# S107X.net
KiCad netlist of a schematic drawn in EAGLE
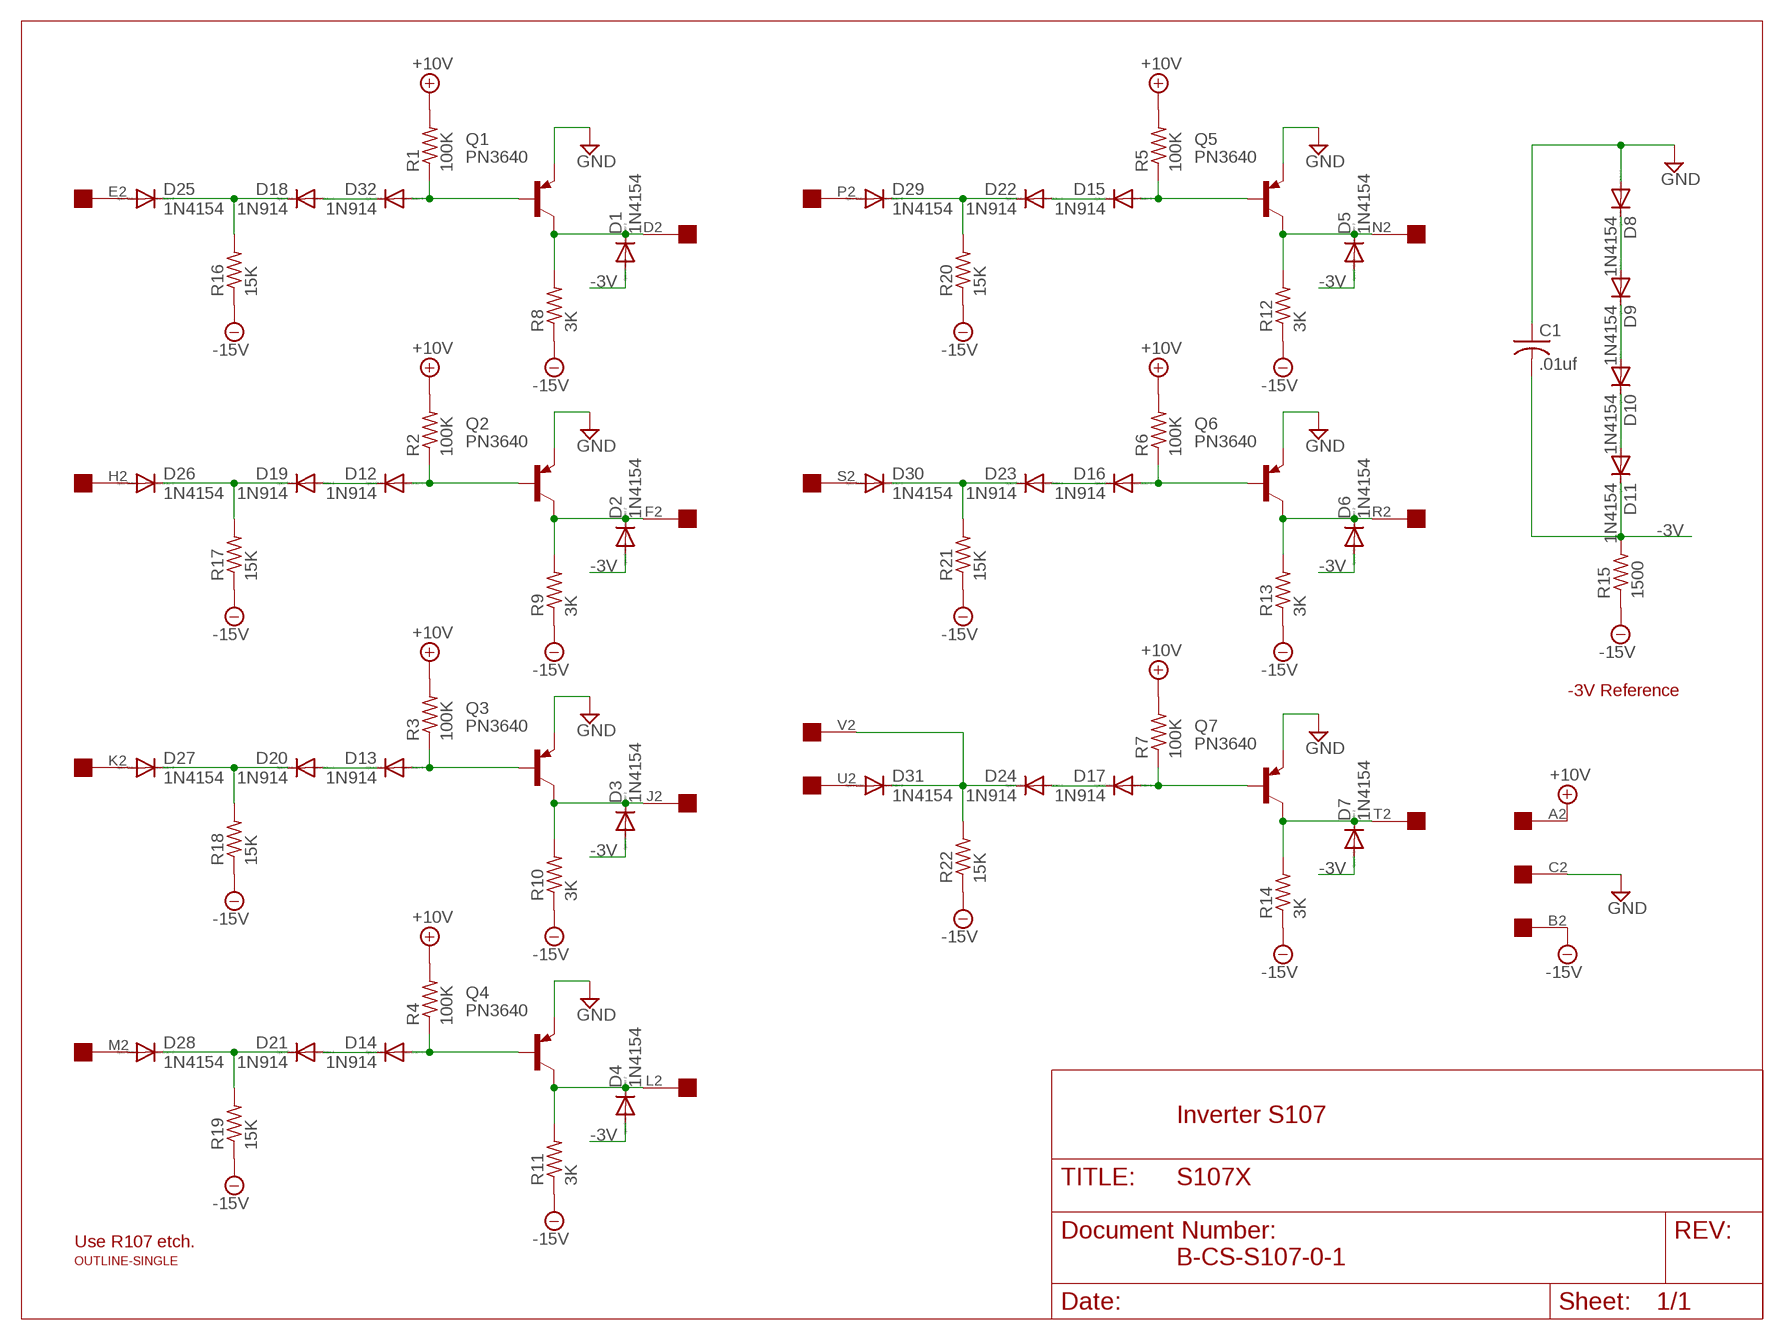
[diagram p0: schematic, sheet 1]

(export (version "E")
  (design (tool "Eeschema 10.0.6"))
  (components
    (comp (ref "C1")
      (value ".01uf")
      (footprint "eagle-import:C050-025X075")
      (libsource (lib "eagle-import") (part "C-US050-025X075"))
    )
    (comp (ref "D1")
      (value "1N4154")
      (footprint "eagle-import:DO35-10")
      (libsource (lib "eagle-import") (part "1N4148DO35-10"))
    )
    (comp (ref "D2")
      (value "1N4154")
      (footprint "eagle-import:DO35-10")
      (libsource (lib "eagle-import") (part "1N4148DO35-10"))
    )
    (comp (ref "D3")
      (value "1N4154")
      (footprint "eagle-import:DO35-10")
      (libsource (lib "eagle-import") (part "1N4148DO35-10"))
    )
    (comp (ref "D4")
      (value "1N4154")
      (footprint "eagle-import:DO35-10")
      (libsource (lib "eagle-import") (part "1N4148DO35-10"))
    )
    (comp (ref "D5")
      (value "1N4154")
      (footprint "eagle-import:DO35-10")
      (libsource (lib "eagle-import") (part "1N4148DO35-10"))
    )
    (comp (ref "D6")
      (value "1N4154")
      (footprint "eagle-import:DO35-10")
      (libsource (lib "eagle-import") (part "1N4148DO35-10"))
    )
    (comp (ref "D7")
      (value "1N4154")
      (footprint "eagle-import:DO35-10")
      (libsource (lib "eagle-import") (part "1N4148DO35-10"))
    )
    (comp (ref "D8")
      (value "1N4154")
      (footprint "eagle-import:DO35-10")
      (libsource (lib "eagle-import") (part "1N4148DO35-10"))
    )
    (comp (ref "D9")
      (value "1N4154")
      (footprint "eagle-import:DO35-10")
      (libsource (lib "eagle-import") (part "1N4148DO35-10"))
    )
    (comp (ref "D10")
      (value "1N4154")
      (footprint "eagle-import:DO35-10")
      (libsource (lib "eagle-import") (part "1N4148DO35-10"))
    )
    (comp (ref "D11")
      (value "1N4154")
      (footprint "eagle-import:DO35-10")
      (libsource (lib "eagle-import") (part "1N4148DO35-10"))
    )
    (comp (ref "D12")
      (value "1N914")
      (footprint "eagle-import:DO35-10")
      (libsource (lib "eagle-import") (part "1N4148DO35-10"))
    )
    (comp (ref "D13")
      (value "1N914")
      (footprint "eagle-import:DO35-10")
      (libsource (lib "eagle-import") (part "1N4148DO35-10"))
    )
    (comp (ref "D14")
      (value "1N914")
      (footprint "eagle-import:DO35-10")
      (libsource (lib "eagle-import") (part "1N4148DO35-10"))
    )
    (comp (ref "D15")
      (value "1N914")
      (footprint "eagle-import:DO35-10")
      (libsource (lib "eagle-import") (part "1N4148DO35-10"))
    )
    (comp (ref "D16")
      (value "1N914")
      (footprint "eagle-import:DO35-10")
      (libsource (lib "eagle-import") (part "1N4148DO35-10"))
    )
    (comp (ref "D17")
      (value "1N914")
      (footprint "eagle-import:DO35-10")
      (libsource (lib "eagle-import") (part "1N4148DO35-10"))
    )
    (comp (ref "D18")
      (value "1N914")
      (footprint "eagle-import:DO35-10")
      (libsource (lib "eagle-import") (part "1N4148DO35-10"))
    )
    (comp (ref "D19")
      (value "1N914")
      (footprint "eagle-import:DO35-10")
      (libsource (lib "eagle-import") (part "1N4148DO35-10"))
    )
    (comp (ref "D20")
      (value "1N914")
      (footprint "eagle-import:DO35-10")
      (libsource (lib "eagle-import") (part "1N4148DO35-10"))
    )
    (comp (ref "D21")
      (value "1N914")
      (footprint "eagle-import:DO35-10")
      (libsource (lib "eagle-import") (part "1N4148DO35-10"))
    )
    (comp (ref "D22")
      (value "1N914")
      (footprint "eagle-import:DO35-10")
      (libsource (lib "eagle-import") (part "1N4148DO35-10"))
    )
    (comp (ref "D23")
      (value "1N914")
      (footprint "eagle-import:DO35-10")
      (libsource (lib "eagle-import") (part "1N4148DO35-10"))
    )
    (comp (ref "D24")
      (value "1N914")
      (footprint "eagle-import:DO35-10")
      (libsource (lib "eagle-import") (part "1N4148DO35-10"))
    )
    (comp (ref "D25")
      (value "1N4154")
      (footprint "eagle-import:DO35-10")
      (libsource (lib "eagle-import") (part "1N4148DO35-10"))
    )
    (comp (ref "D26")
      (value "1N4154")
      (footprint "eagle-import:DO35-10")
      (libsource (lib "eagle-import") (part "1N4148DO35-10"))
    )
    (comp (ref "D27")
      (value "1N4154")
      (footprint "eagle-import:DO35-10")
      (libsource (lib "eagle-import") (part "1N4148DO35-10"))
    )
    (comp (ref "D28")
      (value "1N4154")
      (footprint "eagle-import:DO35-10")
      (libsource (lib "eagle-import") (part "1N4148DO35-10"))
    )
    (comp (ref "D29")
      (value "1N4154")
      (footprint "eagle-import:DO35-10")
      (libsource (lib "eagle-import") (part "1N4148DO35-10"))
    )
    (comp (ref "D30")
      (value "1N4154")
      (footprint "eagle-import:DO35-10")
      (libsource (lib "eagle-import") (part "1N4148DO35-10"))
    )
    (comp (ref "D31")
      (value "1N4154")
      (footprint "eagle-import:DO35-10")
      (libsource (lib "eagle-import") (part "1N4148DO35-10"))
    )
    (comp (ref "D32")
      (value "1N914")
      (footprint "eagle-import:DO35-10")
      (libsource (lib "eagle-import") (part "1N4148DO35-10"))
    )
    (comp (ref "Q1")
      (value "PN3640")
      (footprint "eagle-import:TO39")
      (libsource (lib "eagle-import") (part "2N3637"))
    )
    (comp (ref "Q2")
      (value "PN3640")
      (footprint "eagle-import:TO39")
      (libsource (lib "eagle-import") (part "2N3637"))
    )
    (comp (ref "Q3")
      (value "PN3640")
      (footprint "eagle-import:TO39")
      (libsource (lib "eagle-import") (part "2N3637"))
    )
    (comp (ref "Q4")
      (value "PN3640")
      (footprint "eagle-import:TO39")
      (libsource (lib "eagle-import") (part "2N3637"))
    )
    (comp (ref "Q5")
      (value "PN3640")
      (footprint "eagle-import:TO39")
      (libsource (lib "eagle-import") (part "2N3637"))
    )
    (comp (ref "Q6")
      (value "PN3640")
      (footprint "eagle-import:TO39")
      (libsource (lib "eagle-import") (part "2N3637"))
    )
    (comp (ref "Q7")
      (value "PN3640")
      (footprint "eagle-import:TO39")
      (libsource (lib "eagle-import") (part "2N3637"))
    )
    (comp (ref "R1")
      (value "100K")
      (footprint "eagle-import:0207_10")
      (libsource (lib "eagle-import") (part "R-US_0207/10"))
    )
    (comp (ref "R2")
      (value "100K")
      (footprint "eagle-import:0207_10")
      (libsource (lib "eagle-import") (part "R-US_0207/10"))
    )
    (comp (ref "R3")
      (value "100K")
      (footprint "eagle-import:0207_10")
      (libsource (lib "eagle-import") (part "R-US_0207/10"))
    )
    (comp (ref "R4")
      (value "100K")
      (footprint "eagle-import:0207_10")
      (libsource (lib "eagle-import") (part "R-US_0207/10"))
    )
    (comp (ref "R5")
      (value "100K")
      (footprint "eagle-import:0207_10")
      (libsource (lib "eagle-import") (part "R-US_0207/10"))
    )
    (comp (ref "R6")
      (value "100K")
      (footprint "eagle-import:0207_10")
      (libsource (lib "eagle-import") (part "R-US_0207/10"))
    )
    (comp (ref "R7")
      (value "100K")
      (footprint "eagle-import:0207_10")
      (libsource (lib "eagle-import") (part "R-US_0207/10"))
    )
    (comp (ref "R8")
      (value "3K")
      (footprint "eagle-import:0207_10")
      (libsource (lib "eagle-import") (part "R-US_0207/10"))
    )
    (comp (ref "R9")
      (value "3K")
      (footprint "eagle-import:0207_10")
      (libsource (lib "eagle-import") (part "R-US_0207/10"))
    )
    (comp (ref "R10")
      (value "3K")
      (footprint "eagle-import:0207_10")
      (libsource (lib "eagle-import") (part "R-US_0207/10"))
    )
    (comp (ref "R11")
      (value "3K")
      (footprint "eagle-import:0207_10")
      (libsource (lib "eagle-import") (part "R-US_0207/10"))
    )
    (comp (ref "R12")
      (value "3K")
      (footprint "eagle-import:0207_10")
      (libsource (lib "eagle-import") (part "R-US_0207/10"))
    )
    (comp (ref "R13")
      (value "3K")
      (footprint "eagle-import:0207_10")
      (libsource (lib "eagle-import") (part "R-US_0207/10"))
    )
    (comp (ref "R14")
      (value "3K")
      (footprint "eagle-import:0207_10")
      (libsource (lib "eagle-import") (part "R-US_0207/10"))
    )
    (comp (ref "R15")
      (value "1500")
      (footprint "eagle-import:0207_10")
      (libsource (lib "eagle-import") (part "R-US_0207/10"))
    )
    (comp (ref "R16")
      (value "15K")
      (footprint "eagle-import:0207_10")
      (libsource (lib "eagle-import") (part "R-US_0207/10"))
    )
    (comp (ref "R17")
      (value "15K")
      (footprint "eagle-import:0207_10")
      (libsource (lib "eagle-import") (part "R-US_0207/10"))
    )
    (comp (ref "R18")
      (value "15K")
      (footprint "eagle-import:0207_10")
      (libsource (lib "eagle-import") (part "R-US_0207/10"))
    )
    (comp (ref "R19")
      (value "15K")
      (footprint "eagle-import:0207_10")
      (libsource (lib "eagle-import") (part "R-US_0207/10"))
    )
    (comp (ref "R20")
      (value "15K")
      (footprint "eagle-import:0207_10")
      (libsource (lib "eagle-import") (part "R-US_0207/10"))
    )
    (comp (ref "R21")
      (value "15K")
      (footprint "eagle-import:0207_10")
      (libsource (lib "eagle-import") (part "R-US_0207/10"))
    )
    (comp (ref "R22")
      (value "15K")
      (footprint "eagle-import:0207_10")
      (libsource (lib "eagle-import") (part "R-US_0207/10"))
    )
    (comp (ref "U$1")
      (value "OUTLINE-SINGLE")
      (footprint "eagle-import:SINGLE")
      (libsource (lib "eagle-import") (part "OUTLINE-SINGLE"))
    )
    (comp (ref "U$2")
      (value "EDGE-1")
      (footprint "eagle-import:EDGE-CON1")
      (libsource (lib "eagle-import") (part "EDGE-1"))
    )
  )
  (nets
    (net (code "1") (name "+10V") (class "Default")
      (node (ref "R1") (pin "2") (pinfunction "2_2") (pintype "passive"))
      (node (ref "R2") (pin "2") (pinfunction "2_2") (pintype "passive"))
      (node (ref "R3") (pin "2") (pinfunction "2_2") (pintype "passive"))
      (node (ref "R4") (pin "2") (pinfunction "2_2") (pintype "passive"))
      (node (ref "R5") (pin "2") (pinfunction "2_2") (pintype "passive"))
      (node (ref "R6") (pin "2") (pinfunction "2_2") (pintype "passive"))
      (node (ref "R7") (pin "2") (pinfunction "2_2") (pintype "passive"))
      (node (ref "U$2") (pin "A2") (pinfunction "1_A2") (pintype "bidirectional"))
    )
    (net (code "2") (name "-15V") (class "Default")
      (node (ref "R10") (pin "1") (pinfunction "1_1") (pintype "passive"))
      (node (ref "R11") (pin "1") (pinfunction "1_1") (pintype "passive"))
      (node (ref "R12") (pin "1") (pinfunction "1_1") (pintype "passive"))
      (node (ref "R13") (pin "1") (pinfunction "1_1") (pintype "passive"))
      (node (ref "R14") (pin "1") (pinfunction "1_1") (pintype "passive"))
      (node (ref "R15") (pin "1") (pinfunction "1_1") (pintype "passive"))
      (node (ref "R16") (pin "1") (pinfunction "1_1") (pintype "passive"))
      (node (ref "R17") (pin "1") (pinfunction "1_1") (pintype "passive"))
      (node (ref "R18") (pin "1") (pinfunction "1_1") (pintype "passive"))
      (node (ref "R19") (pin "1") (pinfunction "1_1") (pintype "passive"))
      (node (ref "R20") (pin "1") (pinfunction "1_1") (pintype "passive"))
      (node (ref "R21") (pin "1") (pinfunction "1_1") (pintype "passive"))
      (node (ref "R22") (pin "1") (pinfunction "1_1") (pintype "passive"))
      (node (ref "R8") (pin "1") (pinfunction "1_1") (pintype "passive"))
      (node (ref "R9") (pin "1") (pinfunction "1_1") (pintype "passive"))
      (node (ref "U$2") (pin "B2") (pinfunction "1_B2") (pintype "bidirectional"))
    )
    (net (code "3") (name "/-3V") (class "Default")
      (node (ref "C1") (pin "2") (pinfunction "2_2") (pintype "passive"))
      (node (ref "D1") (pin "A") (pinfunction "A_A") (pintype "passive"))
      (node (ref "D11") (pin "C") (pinfunction "C_C") (pintype "passive"))
      (node (ref "D2") (pin "A") (pinfunction "A_A") (pintype "passive"))
      (node (ref "D3") (pin "A") (pinfunction "A_A") (pintype "passive"))
      (node (ref "D4") (pin "A") (pinfunction "A_A") (pintype "passive"))
      (node (ref "D5") (pin "A") (pinfunction "A_A") (pintype "passive"))
      (node (ref "D6") (pin "A") (pinfunction "A_A") (pintype "passive"))
      (node (ref "D7") (pin "A") (pinfunction "A_A") (pintype "passive"))
      (node (ref "R15") (pin "2") (pinfunction "2_2") (pintype "passive"))
    )
    (net (code "4") (name "GND") (class "Default")
      (node (ref "C1") (pin "1") (pinfunction "1_1") (pintype "passive"))
      (node (ref "D8") (pin "A") (pinfunction "A_A") (pintype "passive"))
      (node (ref "Q1") (pin "1") (pinfunction "E_1") (pintype "passive"))
      (node (ref "Q2") (pin "1") (pinfunction "E_1") (pintype "passive"))
      (node (ref "Q3") (pin "1") (pinfunction "E_1") (pintype "passive"))
      (node (ref "Q4") (pin "1") (pinfunction "E_1") (pintype "passive"))
      (node (ref "Q5") (pin "1") (pinfunction "E_1") (pintype "passive"))
      (node (ref "Q6") (pin "1") (pinfunction "E_1") (pintype "passive"))
      (node (ref "Q7") (pin "1") (pinfunction "E_1") (pintype "passive"))
      (node (ref "U$2") (pin "C2") (pinfunction "1_C2") (pintype "bidirectional"))
    )
    (net (code "5") (name "Net-(D8-PadC)") (class "Default")
      (node (ref "D8") (pin "C") (pinfunction "C_C") (pintype "passive"))
      (node (ref "D9") (pin "A") (pinfunction "A_A") (pintype "passive"))
    )
    (net (code "6") (name "Net-(D10-PadA)") (class "Default")
      (node (ref "D10") (pin "A") (pinfunction "A_A") (pintype "passive"))
      (node (ref "D9") (pin "C") (pinfunction "C_C") (pintype "passive"))
    )
    (net (code "7") (name "Net-(D10-PadC)") (class "Default")
      (node (ref "D10") (pin "C") (pinfunction "C_C") (pintype "passive"))
      (node (ref "D11") (pin "A") (pinfunction "A_A") (pintype "passive"))
    )
    (net (code "8") (name "Net-(D12-PadC)") (class "Default")
      (node (ref "D12") (pin "C") (pinfunction "C_C") (pintype "passive"))
      (node (ref "D19") (pin "A") (pinfunction "A_A") (pintype "passive"))
    )
    (net (code "9") (name "Net-(D13-PadC)") (class "Default")
      (node (ref "D13") (pin "C") (pinfunction "C_C") (pintype "passive"))
      (node (ref "D20") (pin "A") (pinfunction "A_A") (pintype "passive"))
    )
    (net (code "10") (name "Net-(D14-PadC)") (class "Default")
      (node (ref "D14") (pin "C") (pinfunction "C_C") (pintype "passive"))
      (node (ref "D21") (pin "A") (pinfunction "A_A") (pintype "passive"))
    )
    (net (code "11") (name "Net-(D15-PadC)") (class "Default")
      (node (ref "D15") (pin "C") (pinfunction "C_C") (pintype "passive"))
      (node (ref "D22") (pin "A") (pinfunction "A_A") (pintype "passive"))
    )
    (net (code "12") (name "Net-(D16-PadC)") (class "Default")
      (node (ref "D16") (pin "C") (pinfunction "C_C") (pintype "passive"))
      (node (ref "D23") (pin "A") (pinfunction "A_A") (pintype "passive"))
    )
    (net (code "13") (name "Net-(D17-PadC)") (class "Default")
      (node (ref "D17") (pin "C") (pinfunction "C_C") (pintype "passive"))
      (node (ref "D24") (pin "A") (pinfunction "A_A") (pintype "passive"))
    )
    (net (code "14") (name "Net-(D18-PadA)") (class "Default")
      (node (ref "D18") (pin "A") (pinfunction "A_A") (pintype "passive"))
      (node (ref "D32") (pin "C") (pinfunction "C_C") (pintype "passive"))
    )
    (net (code "15") (name "Net-(D18-PadC)") (class "Default")
      (node (ref "D18") (pin "C") (pinfunction "C_C") (pintype "passive"))
      (node (ref "D25") (pin "C") (pinfunction "C_C") (pintype "passive"))
      (node (ref "R16") (pin "2") (pinfunction "2_2") (pintype "passive"))
    )
    (net (code "16") (name "Net-(D19-PadC)") (class "Default")
      (node (ref "D19") (pin "C") (pinfunction "C_C") (pintype "passive"))
      (node (ref "D26") (pin "C") (pinfunction "C_C") (pintype "passive"))
      (node (ref "R17") (pin "2") (pinfunction "2_2") (pintype "passive"))
    )
    (net (code "17") (name "Net-(D20-PadC)") (class "Default")
      (node (ref "D20") (pin "C") (pinfunction "C_C") (pintype "passive"))
      (node (ref "D27") (pin "C") (pinfunction "C_C") (pintype "passive"))
      (node (ref "R18") (pin "2") (pinfunction "2_2") (pintype "passive"))
    )
    (net (code "18") (name "Net-(D21-PadC)") (class "Default")
      (node (ref "D21") (pin "C") (pinfunction "C_C") (pintype "passive"))
      (node (ref "D28") (pin "C") (pinfunction "C_C") (pintype "passive"))
      (node (ref "R19") (pin "2") (pinfunction "2_2") (pintype "passive"))
    )
    (net (code "19") (name "Net-(D22-PadC)") (class "Default")
      (node (ref "D22") (pin "C") (pinfunction "C_C") (pintype "passive"))
      (node (ref "D29") (pin "C") (pinfunction "C_C") (pintype "passive"))
      (node (ref "R20") (pin "2") (pinfunction "2_2") (pintype "passive"))
    )
    (net (code "20") (name "Net-(D23-PadC)") (class "Default")
      (node (ref "D23") (pin "C") (pinfunction "C_C") (pintype "passive"))
      (node (ref "D30") (pin "C") (pinfunction "C_C") (pintype "passive"))
      (node (ref "R21") (pin "2") (pinfunction "2_2") (pintype "passive"))
    )
    (net (code "21") (name "Net-(Q1-B)") (class "Default")
      (node (ref "D32") (pin "A") (pinfunction "A_A") (pintype "passive"))
      (node (ref "Q1") (pin "2") (pinfunction "B_2") (pintype "passive"))
      (node (ref "R1") (pin "1") (pinfunction "1_1") (pintype "passive"))
    )
    (net (code "22") (name "Net-(Q1-C)") (class "Default")
      (node (ref "D1") (pin "C") (pinfunction "C_C") (pintype "passive"))
      (node (ref "Q1") (pin "3") (pinfunction "C_3") (pintype "passive"))
      (node (ref "R8") (pin "2") (pinfunction "2_2") (pintype "passive"))
      (node (ref "U$2") (pin "D2") (pinfunction "1_D2") (pintype "bidirectional"))
    )
    (net (code "23") (name "Net-(Q2-B)") (class "Default")
      (node (ref "D12") (pin "A") (pinfunction "A_A") (pintype "passive"))
      (node (ref "Q2") (pin "2") (pinfunction "B_2") (pintype "passive"))
      (node (ref "R2") (pin "1") (pinfunction "1_1") (pintype "passive"))
    )
    (net (code "24") (name "Net-(Q2-C)") (class "Default")
      (node (ref "D2") (pin "C") (pinfunction "C_C") (pintype "passive"))
      (node (ref "Q2") (pin "3") (pinfunction "C_3") (pintype "passive"))
      (node (ref "R9") (pin "2") (pinfunction "2_2") (pintype "passive"))
      (node (ref "U$2") (pin "F2") (pinfunction "1_F2") (pintype "bidirectional"))
    )
    (net (code "25") (name "Net-(Q3-B)") (class "Default")
      (node (ref "D13") (pin "A") (pinfunction "A_A") (pintype "passive"))
      (node (ref "Q3") (pin "2") (pinfunction "B_2") (pintype "passive"))
      (node (ref "R3") (pin "1") (pinfunction "1_1") (pintype "passive"))
    )
    (net (code "26") (name "Net-(Q3-C)") (class "Default")
      (node (ref "D3") (pin "C") (pinfunction "C_C") (pintype "passive"))
      (node (ref "Q3") (pin "3") (pinfunction "C_3") (pintype "passive"))
      (node (ref "R10") (pin "2") (pinfunction "2_2") (pintype "passive"))
      (node (ref "U$2") (pin "J2") (pinfunction "1_J2") (pintype "bidirectional"))
    )
    (net (code "27") (name "Net-(Q4-B)") (class "Default")
      (node (ref "D14") (pin "A") (pinfunction "A_A") (pintype "passive"))
      (node (ref "Q4") (pin "2") (pinfunction "B_2") (pintype "passive"))
      (node (ref "R4") (pin "1") (pinfunction "1_1") (pintype "passive"))
    )
    (net (code "28") (name "Net-(Q4-C)") (class "Default")
      (node (ref "D4") (pin "C") (pinfunction "C_C") (pintype "passive"))
      (node (ref "Q4") (pin "3") (pinfunction "C_3") (pintype "passive"))
      (node (ref "R11") (pin "2") (pinfunction "2_2") (pintype "passive"))
      (node (ref "U$2") (pin "L2") (pinfunction "1_L2") (pintype "bidirectional"))
    )
    (net (code "29") (name "Net-(Q5-B)") (class "Default")
      (node (ref "D15") (pin "A") (pinfunction "A_A") (pintype "passive"))
      (node (ref "Q5") (pin "2") (pinfunction "B_2") (pintype "passive"))
      (node (ref "R5") (pin "1") (pinfunction "1_1") (pintype "passive"))
    )
    (net (code "30") (name "Net-(Q5-C)") (class "Default")
      (node (ref "D5") (pin "C") (pinfunction "C_C") (pintype "passive"))
      (node (ref "Q5") (pin "3") (pinfunction "C_3") (pintype "passive"))
      (node (ref "R12") (pin "2") (pinfunction "2_2") (pintype "passive"))
      (node (ref "U$2") (pin "N2") (pinfunction "1_N2") (pintype "bidirectional"))
    )
    (net (code "31") (name "Net-(Q6-B)") (class "Default")
      (node (ref "D16") (pin "A") (pinfunction "A_A") (pintype "passive"))
      (node (ref "Q6") (pin "2") (pinfunction "B_2") (pintype "passive"))
      (node (ref "R6") (pin "1") (pinfunction "1_1") (pintype "passive"))
    )
    (net (code "32") (name "Net-(Q6-C)") (class "Default")
      (node (ref "D6") (pin "C") (pinfunction "C_C") (pintype "passive"))
      (node (ref "Q6") (pin "3") (pinfunction "C_3") (pintype "passive"))
      (node (ref "R13") (pin "2") (pinfunction "2_2") (pintype "passive"))
      (node (ref "U$2") (pin "R2") (pinfunction "1_R2") (pintype "bidirectional"))
    )
    (net (code "33") (name "Net-(Q7-B)") (class "Default")
      (node (ref "D17") (pin "A") (pinfunction "A_A") (pintype "passive"))
      (node (ref "Q7") (pin "2") (pinfunction "B_2") (pintype "passive"))
      (node (ref "R7") (pin "1") (pinfunction "1_1") (pintype "passive"))
    )
    (net (code "34") (name "Net-(Q7-C)") (class "Default")
      (node (ref "D7") (pin "C") (pinfunction "C_C") (pintype "passive"))
      (node (ref "Q7") (pin "3") (pinfunction "C_3") (pintype "passive"))
      (node (ref "R14") (pin "2") (pinfunction "2_2") (pintype "passive"))
      (node (ref "U$2") (pin "T2") (pinfunction "1_T2") (pintype "bidirectional"))
    )
    (net (code "35") (name "Net-(U$2E-1)") (class "Default")
      (node (ref "D25") (pin "A") (pinfunction "A_A") (pintype "passive"))
      (node (ref "U$2") (pin "E2") (pinfunction "1_E2") (pintype "bidirectional"))
    )
    (net (code "36") (name "Net-(U$2G-1)") (class "Default")
      (node (ref "D26") (pin "A") (pinfunction "A_A") (pintype "passive"))
      (node (ref "U$2") (pin "H2") (pinfunction "1_H2") (pintype "bidirectional"))
    )
    (net (code "37") (name "Net-(U$2I-1)") (class "Default")
      (node (ref "D27") (pin "A") (pinfunction "A_A") (pintype "passive"))
      (node (ref "U$2") (pin "K2") (pinfunction "1_K2") (pintype "bidirectional"))
    )
    (net (code "38") (name "Net-(U$2K-1)") (class "Default")
      (node (ref "D28") (pin "A") (pinfunction "A_A") (pintype "passive"))
      (node (ref "U$2") (pin "M2") (pinfunction "1_M2") (pintype "bidirectional"))
    )
    (net (code "39") (name "Net-(U$2M-1)") (class "Default")
      (node (ref "D29") (pin "A") (pinfunction "A_A") (pintype "passive"))
      (node (ref "U$2") (pin "P2") (pinfunction "1_P2") (pintype "bidirectional"))
    )
    (net (code "40") (name "Net-(U$2O-1)") (class "Default")
      (node (ref "D30") (pin "A") (pinfunction "A_A") (pintype "passive"))
      (node (ref "U$2") (pin "S2") (pinfunction "1_S2") (pintype "bidirectional"))
    )
    (net (code "41") (name "Net-(U$2Q-1)") (class "Default")
      (node (ref "D31") (pin "A") (pinfunction "A_A") (pintype "passive"))
      (node (ref "U$2") (pin "U2") (pinfunction "1_U2") (pintype "bidirectional"))
    )
    (net (code "42") (name "Net-(U$2R-1)") (class "Default")
      (node (ref "D24") (pin "C") (pinfunction "C_C") (pintype "passive"))
      (node (ref "D31") (pin "C") (pinfunction "C_C") (pintype "passive"))
      (node (ref "R22") (pin "2") (pinfunction "2_2") (pintype "passive"))
      (node (ref "U$2") (pin "V2") (pinfunction "1_V2") (pintype "bidirectional"))
    )
  )
)
